# Sheet1.net
KiCad netlist of a schematic drawn in Altium Designer
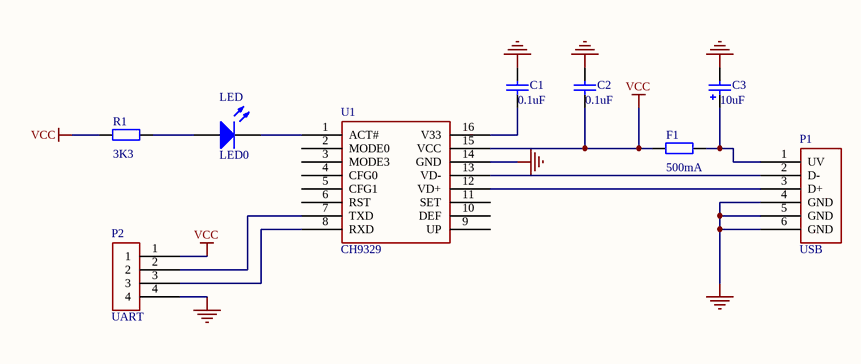
[diagram p0: Sheet1.SchDoc]

(export (version "E")
  (design (tool "Eeschema 10.0.6"))
  (components
    (comp (ref "C1")
      (value "0.1uF")
      (footprint "RAD-0.3")
      (description "Capacitor")
      (fields (field (name "Comment") "Cap") (field (name "PUBLISHER") "Altium Limited"))
      (libsource (lib "Miscellaneous Devices") (part "Cap"))
    )
    (comp (ref "C2")
      (value "0.1uF")
      (footprint "RAD-0.3")
      (description "Capacitor")
      (fields (field (name "Comment") "Cap") (field (name "PUBLISHER") "Altium Limited"))
      (libsource (lib "Miscellaneous Devices") (part "Cap"))
    )
    (comp (ref "C3")
      (value "10uF")
      (footprint "POLAR0.8")
      (description "Polarized Capacitor (Axial)")
      (fields (field (name "Comment") "Cap Pol2") (field (name "PUBLISHER") "Altium Limited"))
      (libsource (lib "Miscellaneous Devices") (part "Cap Pol2"))
    )
    (comp (ref "F1")
      (value "500mA")
      (footprint "AXIAL-0.4")
      (description "Resistor")
      (fields (field (name "Comment") "Res2") (field (name "PUBLISHER") "Altium Limited"))
      (libsource (lib "Miscellaneous Devices") (part "Res2"))
    )
    (comp (ref "LED")
      (value "LED0")
      (footprint "LED-0")
      (description "Typical INFRARED GaAs LED")
      (fields (field (name "PUBLISHER") "Altium Limited"))
      (libsource (lib "Miscellaneous Devices") (part "LED0"))
    )
    (comp (ref "P1") (value "USB") (footprint "USB") (libsource (lib "Schlib1") (part "USB")))
    (comp (ref "P2")
      (value "UART")
      (footprint "UART")
      (description "串口")
      (libsource (lib "Schlib1") (part "UART"))
    )
    (comp (ref "R1")
      (value "3K3")
      (footprint "AXIAL-0.4")
      (description "Resistor")
      (fields (field (name "PUBLISHER") "Altium Limited"))
      (libsource (lib "Miscellaneous Devices") (part "Res2"))
    )
    (comp (ref "U1")
      (value "CH9329")
      (footprint "CH9329")
      (description "主控")
      (libsource (lib "Schlib1") (part "CH9329"))
    )
  )
  (nets
    (net (code "1") (name "GND") (class "Default")
      (node (ref "C1") (pin "2") (pinfunction "2_2") (pintype "passive"))
      (node (ref "C2") (pin "2") (pinfunction "2_2") (pintype "passive"))
      (node (ref "C3") (pin "2") (pinfunction "2_2") (pintype "passive"))
      (node (ref "P1") (pin "4") (pinfunction "GND_4") (pintype "passive"))
      (node (ref "P1") (pin "5") (pinfunction "GND_5") (pintype "passive"))
      (node (ref "P1") (pin "6") (pinfunction "GND_6") (pintype "passive"))
      (node (ref "P2") (pin "4") (pinfunction "4_4") (pintype "passive"))
      (node (ref "U1") (pin "14") (pinfunction "GND_14") (pintype "passive"))
    )
    (net (code "2") (name "Net-(LED-A)") (class "Default")
      (node (ref "LED") (pin "1") (pinfunction "A_1") (pintype "passive"))
      (node (ref "R1") (pin "2") (pinfunction "2_2") (pintype "passive"))
    )
    (net (code "3") (name "Net-(LED-K)") (class "Default")
      (node (ref "LED") (pin "2") (pinfunction "K_2") (pintype "passive"))
      (node (ref "U1") (pin "1") (pinfunction "ACT#_1") (pintype "passive"))
    )
    (net (code "4") (name "Net-(P1-D+)") (class "Default")
      (node (ref "P1") (pin "3") (pinfunction "D+_3") (pintype "passive"))
      (node (ref "U1") (pin "12") (pinfunction "VD+_12") (pintype "passive"))
    )
    (net (code "5") (name "Net-(P1-D-)") (class "Default")
      (node (ref "P1") (pin "2") (pinfunction "D-_2") (pintype "passive"))
      (node (ref "U1") (pin "13") (pinfunction "VD-_13") (pintype "passive"))
    )
    (net (code "6") (name "Net-(P1-UV)") (class "Default")
      (node (ref "C3") (pin "1") (pinfunction "1_1") (pintype "passive"))
      (node (ref "F1") (pin "2") (pinfunction "2_2") (pintype "passive"))
      (node (ref "P1") (pin "1") (pinfunction "UV_1") (pintype "passive"))
    )
    (net (code "7") (name "Net-(U1-RXD)") (class "Default")
      (node (ref "P2") (pin "3") (pinfunction "3_3") (pintype "passive"))
      (node (ref "U1") (pin "8") (pinfunction "RXD_8") (pintype "passive"))
    )
    (net (code "8") (name "Net-(U1-TXD)") (class "Default")
      (node (ref "P2") (pin "2") (pinfunction "2_2") (pintype "passive"))
      (node (ref "U1") (pin "7") (pinfunction "TXD_7") (pintype "passive"))
    )
    (net (code "9") (name "Net-(U1-V33)") (class "Default")
      (node (ref "C1") (pin "1") (pinfunction "1_1") (pintype "passive"))
      (node (ref "U1") (pin "16") (pinfunction "V33_16") (pintype "passive"))
    )
    (net (code "10") (name "VCC") (class "Default")
      (node (ref "C2") (pin "1") (pinfunction "1_1") (pintype "passive"))
      (node (ref "F1") (pin "1") (pinfunction "1_1") (pintype "passive"))
      (node (ref "P2") (pin "1") (pinfunction "1_1") (pintype "passive"))
      (node (ref "R1") (pin "1") (pinfunction "1_1") (pintype "passive"))
      (node (ref "U1") (pin "15") (pinfunction "VCC_15") (pintype "passive"))
    )
    (net (code "11") (name "unconnected-(U1-CFG0-Pad4)") (class "Default")
      (node (ref "U1") (pin "4") (pinfunction "CFG0_4") (pintype "passive"))
    )
    (net (code "12") (name "unconnected-(U1-CFG1-Pad5)") (class "Default")
      (node (ref "U1") (pin "5") (pinfunction "CFG1_5") (pintype "passive"))
    )
    (net (code "13") (name "unconnected-(U1-DEF-Pad10)") (class "Default")
      (node (ref "U1") (pin "10") (pinfunction "DEF_10") (pintype "passive"))
    )
    (net (code "14") (name "unconnected-(U1-MODE0-Pad2)") (class "Default")
      (node (ref "U1") (pin "2") (pinfunction "MODE0_2") (pintype "passive"))
    )
    (net (code "15") (name "unconnected-(U1-MODE3-Pad3)") (class "Default")
      (node (ref "U1") (pin "3") (pinfunction "MODE3_3") (pintype "passive"))
    )
    (net (code "16") (name "unconnected-(U1-RST-Pad6)") (class "Default")
      (node (ref "U1") (pin "6") (pinfunction "RST_6") (pintype "passive"))
    )
    (net (code "17") (name "unconnected-(U1-SET-Pad11)") (class "Default")
      (node (ref "U1") (pin "11") (pinfunction "SET_11") (pintype "passive"))
    )
    (net (code "18") (name "unconnected-(U1-UP-Pad9)") (class "Default")
      (node (ref "U1") (pin "9") (pinfunction "UP_9") (pintype "passive"))
    )
  )
)
